# Arduino_connecions.net
KiCad netlist of a schematic drawn in Altium Designer
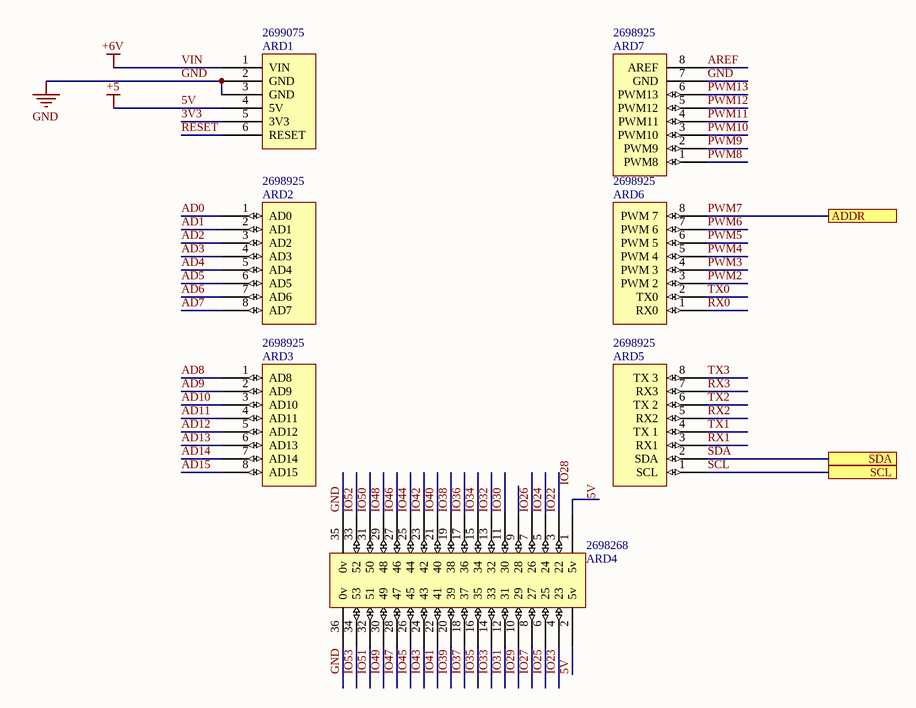
[diagram p0: Arduino connecions.SchDoc]

(export (version "E")
  (design (tool "Eeschema 10.0.6"))
  (components
    (comp (ref "ARD1")
      (value "~")
      (footprint "Header 6x1 8.5mm")
      (description "POWER")
      (fields (field (name "SUPPLIER PART NUMBER 2") "2699075"))
      (libsource (lib "Header") (part "POWER"))
    )
    (comp (ref "ARD2")
      (value "AD_L")
      (footprint "Header 8x1 8.5mm")
      (fields (field (name "SUPPLIER PART NUMBER 5") "2698925"))
      (libsource (lib "Header") (part "AD_L"))
    )
    (comp (ref "ARD3")
      (value "AD_H")
      (footprint "Header 8x1 8.5mm")
      (fields (field (name "SUPPLIER PART NUMBER 4") "2698925"))
      (libsource (lib "Header") (part "AD_H"))
    )
    (comp (ref "ARD4")
      (value "IO_36")
      (footprint "HEADER 36X 8MM")
      (fields (field (name "SUPPLIER PART NUMBER 5") "2698268"))
      (libsource (lib "Header") (part "IO_36"))
    )
    (comp (ref "ARD5")
      (value "Communication")
      (footprint "Header 8x1 8.5mm")
      (fields (field (name "SUPPLIER PART NUMBER 4") "2698925"))
      (libsource (lib "Header") (part "Communication"))
    )
    (comp (ref "ARD6")
      (value "PWM_L")
      (footprint "Header 8x1 8.5mm")
      (fields (field (name "SUPPLIER PART NUMBER 4") "2698925"))
      (libsource (lib "Header") (part "PWM_L"))
    )
    (comp (ref "ARD7")
      (value "PWM_H")
      (footprint "Header 8x1 8.5mm")
      (fields (field (name "SUPPLIER PART NUMBER 4") "2698925"))
      (libsource (lib "Header") (part "PWM_H"))
    )
  )
  (nets
    (net (code "1") (name "+5") (class "Default")
      (node (ref "ARD1") (pin "4") (pinfunction "5V_4") (pintype "power_in"))
      (node (ref "ARD4") (pin "1") (pinfunction "5v_1") (pintype "power_in"))
      (node (ref "ARD4") (pin "2") (pinfunction "5v_2") (pintype "power_in"))
    )
    (net (code "2") (name "+6V") (class "Default")
      (node (ref "ARD1") (pin "1") (pinfunction "VIN_1") (pintype "power_in"))
    )
    (net (code "3") (name "/3V3") (class "Default")
      (node (ref "ARD1") (pin "5") (pinfunction "3V3_5") (pintype "power_in"))
    )
    (net (code "4") (name "/AD0") (class "Default")
      (node (ref "ARD2") (pin "1") (pinfunction "AD0_1") (pintype "bidirectional"))
    )
    (net (code "5") (name "/AD1") (class "Default")
      (node (ref "ARD2") (pin "2") (pinfunction "AD1_2") (pintype "bidirectional"))
    )
    (net (code "6") (name "/AD2") (class "Default")
      (node (ref "ARD2") (pin "3") (pinfunction "AD2_3") (pintype "bidirectional"))
    )
    (net (code "7") (name "/AD3") (class "Default")
      (node (ref "ARD2") (pin "4") (pinfunction "AD3_4") (pintype "bidirectional"))
    )
    (net (code "8") (name "/AD4") (class "Default")
      (node (ref "ARD2") (pin "5") (pinfunction "AD4_5") (pintype "bidirectional"))
    )
    (net (code "9") (name "/AD5") (class "Default")
      (node (ref "ARD2") (pin "6") (pinfunction "AD5_6") (pintype "bidirectional"))
    )
    (net (code "10") (name "/AD6") (class "Default")
      (node (ref "ARD2") (pin "7") (pinfunction "AD6_7") (pintype "bidirectional"))
    )
    (net (code "11") (name "/AD7") (class "Default")
      (node (ref "ARD2") (pin "8") (pinfunction "AD7_8") (pintype "bidirectional"))
    )
    (net (code "12") (name "/AD8") (class "Default")
      (node (ref "ARD3") (pin "1") (pinfunction "AD8_1") (pintype "bidirectional"))
    )
    (net (code "13") (name "/AD9") (class "Default")
      (node (ref "ARD3") (pin "2") (pinfunction "AD9_2") (pintype "bidirectional"))
    )
    (net (code "14") (name "/AD10") (class "Default")
      (node (ref "ARD3") (pin "3") (pinfunction "AD10_3") (pintype "bidirectional"))
    )
    (net (code "15") (name "/AD11") (class "Default")
      (node (ref "ARD3") (pin "4") (pinfunction "AD11_4") (pintype "bidirectional"))
    )
    (net (code "16") (name "/AD12") (class "Default")
      (node (ref "ARD3") (pin "5") (pinfunction "AD12_5") (pintype "bidirectional"))
    )
    (net (code "17") (name "/AD13") (class "Default")
      (node (ref "ARD3") (pin "6") (pinfunction "AD13_6") (pintype "bidirectional"))
    )
    (net (code "18") (name "/AD14") (class "Default")
      (node (ref "ARD3") (pin "7") (pinfunction "AD14_7") (pintype "bidirectional"))
    )
    (net (code "19") (name "/AD15") (class "Default")
      (node (ref "ARD3") (pin "8") (pinfunction "AD15_8") (pintype "bidirectional"))
    )
    (net (code "20") (name "/AREF") (class "Default")
      (node (ref "ARD7") (pin "8") (pinfunction "AREF_8") (pintype "passive"))
    )
    (net (code "21") (name "/IO22") (class "Default")
      (node (ref "ARD4") (pin "3") (pinfunction "22_3") (pintype "bidirectional"))
    )
    (net (code "22") (name "/IO23") (class "Default")
      (node (ref "ARD4") (pin "4") (pinfunction "23_4") (pintype "bidirectional"))
    )
    (net (code "23") (name "/IO24") (class "Default")
      (node (ref "ARD4") (pin "5") (pinfunction "24_5") (pintype "bidirectional"))
    )
    (net (code "24") (name "/IO25") (class "Default")
      (node (ref "ARD4") (pin "6") (pinfunction "25_6") (pintype "bidirectional"))
    )
    (net (code "25") (name "/IO26") (class "Default")
      (node (ref "ARD4") (pin "7") (pinfunction "26_7") (pintype "bidirectional"))
    )
    (net (code "26") (name "/IO27") (class "Default")
      (node (ref "ARD4") (pin "8") (pinfunction "27_8") (pintype "bidirectional"))
    )
    (net (code "28") (name "/IO29") (class "Default")
      (node (ref "ARD4") (pin "10") (pinfunction "29_10") (pintype "bidirectional"))
    )
    (net (code "29") (name "/IO30") (class "Default")
      (node (ref "ARD4") (pin "11") (pinfunction "30_11") (pintype "bidirectional"))
    )
    (net (code "30") (name "/IO31") (class "Default")
      (node (ref "ARD4") (pin "12") (pinfunction "31_12") (pintype "bidirectional"))
    )
    (net (code "31") (name "/IO32") (class "Default")
      (node (ref "ARD4") (pin "13") (pinfunction "32_13") (pintype "bidirectional"))
    )
    (net (code "32") (name "/IO33") (class "Default")
      (node (ref "ARD4") (pin "14") (pinfunction "33_14") (pintype "bidirectional"))
    )
    (net (code "33") (name "/IO34") (class "Default")
      (node (ref "ARD4") (pin "15") (pinfunction "34_15") (pintype "bidirectional"))
    )
    (net (code "34") (name "/IO35") (class "Default")
      (node (ref "ARD4") (pin "16") (pinfunction "35_16") (pintype "bidirectional"))
    )
    (net (code "35") (name "/IO36") (class "Default")
      (node (ref "ARD4") (pin "17") (pinfunction "36_17") (pintype "bidirectional"))
    )
    (net (code "36") (name "/IO37") (class "Default")
      (node (ref "ARD4") (pin "18") (pinfunction "37_18") (pintype "bidirectional"))
    )
    (net (code "37") (name "/IO38") (class "Default")
      (node (ref "ARD4") (pin "19") (pinfunction "38_19") (pintype "bidirectional"))
    )
    (net (code "38") (name "/IO39") (class "Default")
      (node (ref "ARD4") (pin "20") (pinfunction "39_20") (pintype "bidirectional"))
    )
    (net (code "39") (name "/IO40") (class "Default")
      (node (ref "ARD4") (pin "21") (pinfunction "40_21") (pintype "bidirectional"))
    )
    (net (code "40") (name "/IO41") (class "Default")
      (node (ref "ARD4") (pin "22") (pinfunction "41_22") (pintype "bidirectional"))
    )
    (net (code "41") (name "/IO42") (class "Default")
      (node (ref "ARD4") (pin "23") (pinfunction "42_23") (pintype "bidirectional"))
    )
    (net (code "42") (name "/IO43") (class "Default")
      (node (ref "ARD4") (pin "24") (pinfunction "43_24") (pintype "bidirectional"))
    )
    (net (code "43") (name "/IO44") (class "Default")
      (node (ref "ARD4") (pin "25") (pinfunction "44_25") (pintype "bidirectional"))
    )
    (net (code "44") (name "/IO45") (class "Default")
      (node (ref "ARD4") (pin "26") (pinfunction "45_26") (pintype "bidirectional"))
    )
    (net (code "45") (name "/IO46") (class "Default")
      (node (ref "ARD4") (pin "27") (pinfunction "46_27") (pintype "bidirectional"))
    )
    (net (code "46") (name "/IO47") (class "Default")
      (node (ref "ARD4") (pin "28") (pinfunction "47_28") (pintype "bidirectional"))
    )
    (net (code "47") (name "/IO48") (class "Default")
      (node (ref "ARD4") (pin "29") (pinfunction "48_29") (pintype "bidirectional"))
    )
    (net (code "48") (name "/IO49") (class "Default")
      (node (ref "ARD4") (pin "30") (pinfunction "49_30") (pintype "bidirectional"))
    )
    (net (code "49") (name "/IO50") (class "Default")
      (node (ref "ARD4") (pin "31") (pinfunction "50_31") (pintype "bidirectional"))
    )
    (net (code "50") (name "/IO51") (class "Default")
      (node (ref "ARD4") (pin "32") (pinfunction "51_32") (pintype "bidirectional"))
    )
    (net (code "51") (name "/IO52") (class "Default")
      (node (ref "ARD4") (pin "33") (pinfunction "52_33") (pintype "bidirectional"))
    )
    (net (code "52") (name "/IO53") (class "Default")
      (node (ref "ARD4") (pin "34") (pinfunction "53_34") (pintype "bidirectional"))
    )
    (net (code "53") (name "/PWM2") (class "Default")
      (node (ref "ARD6") (pin "3") (pinfunction "PWM_2_3") (pintype "bidirectional"))
    )
    (net (code "54") (name "/PWM3") (class "Default")
      (node (ref "ARD6") (pin "4") (pinfunction "PWM_3_4") (pintype "bidirectional"))
    )
    (net (code "55") (name "/PWM4") (class "Default")
      (node (ref "ARD6") (pin "5") (pinfunction "PWM_4_5") (pintype "bidirectional"))
    )
    (net (code "56") (name "/PWM5") (class "Default")
      (node (ref "ARD6") (pin "6") (pinfunction "PWM_5_6") (pintype "bidirectional"))
    )
    (net (code "57") (name "/PWM6") (class "Default")
      (node (ref "ARD6") (pin "7") (pinfunction "PWM_6_7") (pintype "bidirectional"))
    )
    (net (code "58") (name "/PWM7") (class "Default")
      (node (ref "ARD6") (pin "8") (pinfunction "PWM_7_8") (pintype "bidirectional"))
    )
    (net (code "59") (name "/PWM8") (class "Default")
      (node (ref "ARD7") (pin "1") (pinfunction "PWM8_1") (pintype "bidirectional"))
    )
    (net (code "60") (name "/PWM9") (class "Default")
      (node (ref "ARD7") (pin "2") (pinfunction "PWM9_2") (pintype "bidirectional"))
    )
    (net (code "61") (name "/PWM10") (class "Default")
      (node (ref "ARD7") (pin "3") (pinfunction "PWM10_3") (pintype "bidirectional"))
    )
    (net (code "62") (name "/PWM11") (class "Default")
      (node (ref "ARD7") (pin "4") (pinfunction "PWM11_4") (pintype "bidirectional"))
    )
    (net (code "63") (name "/PWM12") (class "Default")
      (node (ref "ARD7") (pin "5") (pinfunction "PWM12_5") (pintype "bidirectional"))
    )
    (net (code "64") (name "/PWM13") (class "Default")
      (node (ref "ARD7") (pin "6") (pinfunction "PWM13_6") (pintype "bidirectional"))
    )
    (net (code "65") (name "/RESET") (class "Default")
      (node (ref "ARD1") (pin "6") (pinfunction "RESET_6") (pintype "passive"))
    )
    (net (code "66") (name "/RX0") (class "Default")
      (node (ref "ARD6") (pin "1") (pinfunction "RX0_1") (pintype "bidirectional"))
    )
    (net (code "67") (name "/RX1") (class "Default")
      (node (ref "ARD5") (pin "3") (pinfunction "RX1_3") (pintype "bidirectional"))
    )
    (net (code "68") (name "/RX2") (class "Default")
      (node (ref "ARD5") (pin "5") (pinfunction "RX2_5") (pintype "bidirectional"))
    )
    (net (code "69") (name "/RX3") (class "Default")
      (node (ref "ARD5") (pin "7") (pinfunction "RX3_7") (pintype "bidirectional"))
    )
    (net (code "70") (name "/SCL") (class "Default")
      (node (ref "ARD5") (pin "1") (pinfunction "SCL_1") (pintype "bidirectional"))
    )
    (net (code "71") (name "/SDA") (class "Default")
      (node (ref "ARD5") (pin "2") (pinfunction "SDA_2") (pintype "bidirectional"))
    )
    (net (code "72") (name "/TX0") (class "Default")
      (node (ref "ARD6") (pin "2") (pinfunction "TX0_2") (pintype "bidirectional"))
    )
    (net (code "73") (name "/TX1") (class "Default")
      (node (ref "ARD5") (pin "4") (pinfunction "TX_1_4") (pintype "bidirectional"))
    )
    (net (code "74") (name "/TX2") (class "Default")
      (node (ref "ARD5") (pin "6") (pinfunction "TX_2_6") (pintype "bidirectional"))
    )
    (net (code "75") (name "/TX3") (class "Default")
      (node (ref "ARD5") (pin "8") (pinfunction "TX_3_8") (pintype "bidirectional"))
    )
    (net (code "76") (name "GND") (class "Default")
      (node (ref "ARD1") (pin "2") (pinfunction "GND_2") (pintype "power_in"))
      (node (ref "ARD1") (pin "3") (pinfunction "GND_3") (pintype "power_in"))
      (node (ref "ARD4") (pin "35") (pinfunction "0v_35") (pintype "power_in"))
      (node (ref "ARD4") (pin "36") (pinfunction "0v_36") (pintype "power_in"))
      (node (ref "ARD7") (pin "7") (pinfunction "GND_7") (pintype "power_in"))
    )
    (net (code "77") (name "unconnected-(ARD4-28-Pad9)") (class "Default")
      (node (ref "ARD4") (pin "9") (pinfunction "28_9") (pintype "bidirectional"))
    )
  )
)
